# Nucleo.net
KiCad netlist of a schematic drawn in Altium Designer
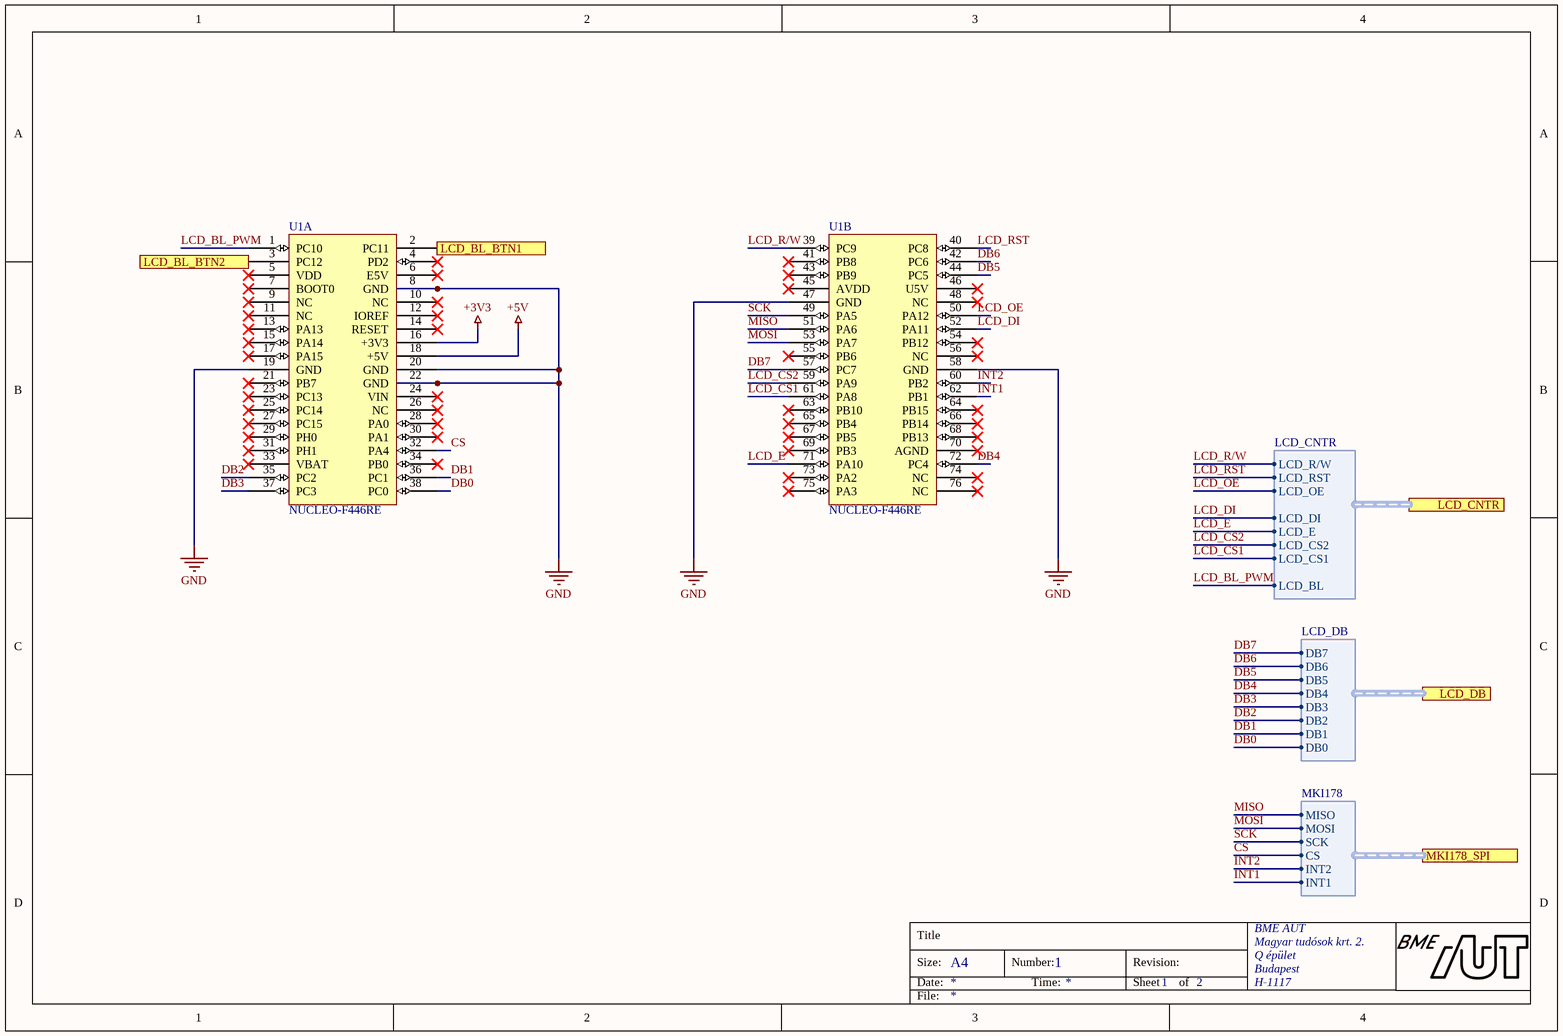
[diagram p0: Nucleo.SchDoc]

(export (version "E")
  (design (tool "Eeschema 10.0.6"))
  (components
    (comp (ref "U1")
      (value "NUCLEO-F446RE")
      (footprint "FP_NUCLEO-64")
      (libsource (lib "hallglib") (part "NUCLEO-F446RE"))
    )
  )
  (nets
    (net (code "4") (name "+3V3") (class "Default")
      (node (ref "U1") (pin "16") (pinfunction "+3V3_16") (pintype "power_in"))
    )
    (net (code "5") (name "+5V") (class "Default")
      (node (ref "U1") (pin "18") (pinfunction "+5V_18") (pintype "power_in"))
    )
    (net (code "6") (name "/CS") (class "Default")
      (node (ref "U1") (pin "32") (pinfunction "PA4_32") (pintype "bidirectional"))
    )
    (net (code "7") (name "/DB0") (class "Default")
      (node (ref "U1") (pin "38") (pinfunction "PC0_38") (pintype "bidirectional"))
    )
    (net (code "8") (name "/DB1") (class "Default")
      (node (ref "U1") (pin "36") (pinfunction "PC1_36") (pintype "bidirectional"))
    )
    (net (code "9") (name "/DB2") (class "Default")
      (node (ref "U1") (pin "35") (pinfunction "PC2_35") (pintype "bidirectional"))
    )
    (net (code "10") (name "/DB3") (class "Default")
      (node (ref "U1") (pin "37") (pinfunction "PC3_37") (pintype "bidirectional"))
    )
    (net (code "11") (name "/DB4") (class "Default")
      (node (ref "U1") (pin "72") (pinfunction "PC4_72") (pintype "bidirectional"))
    )
    (net (code "12") (name "/DB5") (class "Default")
      (node (ref "U1") (pin "44") (pinfunction "PC5_44") (pintype "bidirectional"))
    )
    (net (code "13") (name "/DB6") (class "Default")
      (node (ref "U1") (pin "42") (pinfunction "PC6_42") (pintype "bidirectional"))
    )
    (net (code "14") (name "/DB7") (class "Default")
      (node (ref "U1") (pin "57") (pinfunction "PC7_57") (pintype "bidirectional"))
    )
    (net (code "15") (name "/INT1") (class "Default")
      (node (ref "U1") (pin "62") (pinfunction "PB1_62") (pintype "bidirectional"))
    )
    (net (code "16") (name "/INT2") (class "Default")
      (node (ref "U1") (pin "60") (pinfunction "PB2_60") (pintype "bidirectional"))
    )
    (net (code "17") (name "/LCD_BL_BTN1") (class "Default")
      (node (ref "U1") (pin "2") (pinfunction "PC11_2") (pintype "passive"))
    )
    (net (code "18") (name "/LCD_BL_BTN2") (class "Default")
      (node (ref "U1") (pin "3") (pinfunction "PC12_3") (pintype "passive"))
    )
    (net (code "19") (name "/LCD_BL_PWM") (class "Default")
      (node (ref "U1") (pin "1") (pinfunction "PC10_1") (pintype "bidirectional"))
    )
    (net (code "20") (name "/LCD_CS1") (class "Default")
      (node (ref "U1") (pin "61") (pinfunction "PA8_61") (pintype "bidirectional"))
    )
    (net (code "21") (name "/LCD_CS2") (class "Default")
      (node (ref "U1") (pin "59") (pinfunction "PA9_59") (pintype "bidirectional"))
    )
    (net (code "22") (name "/LCD_DI") (class "Default")
      (node (ref "U1") (pin "52") (pinfunction "PA11_52") (pintype "bidirectional"))
    )
    (net (code "23") (name "/LCD_E") (class "Default")
      (node (ref "U1") (pin "71") (pinfunction "PA10_71") (pintype "bidirectional"))
    )
    (net (code "24") (name "/LCD_OE") (class "Default")
      (node (ref "U1") (pin "50") (pinfunction "PA12_50") (pintype "bidirectional"))
    )
    (net (code "25") (name "/LCD_RST") (class "Default")
      (node (ref "U1") (pin "40") (pinfunction "PC8_40") (pintype "bidirectional"))
    )
    (net (code "26") (name "/LCD_R{slash}W") (class "Default")
      (node (ref "U1") (pin "39") (pinfunction "PC9_39") (pintype "bidirectional"))
    )
    (net (code "27") (name "/MISO") (class "Default")
      (node (ref "U1") (pin "51") (pinfunction "PA6_51") (pintype "bidirectional"))
    )
    (net (code "28") (name "/MOSI") (class "Default")
      (node (ref "U1") (pin "53") (pinfunction "PA7_53") (pintype "bidirectional"))
    )
    (net (code "29") (name "/SCK") (class "Default")
      (node (ref "U1") (pin "49") (pinfunction "PA5_49") (pintype "bidirectional"))
    )
    (net (code "33") (name "GND") (class "Default")
      (node (ref "U1") (pin "19") (pinfunction "GND_19") (pintype "passive"))
      (node (ref "U1") (pin "20") (pinfunction "GND_20") (pintype "passive"))
      (node (ref "U1") (pin "22") (pinfunction "GND_22") (pintype "passive"))
      (node (ref "U1") (pin "47") (pinfunction "GND_47") (pintype "passive"))
      (node (ref "U1") (pin "58") (pinfunction "GND_58") (pintype "passive"))
      (node (ref "U1") (pin "8") (pinfunction "GND_8") (pintype "passive"))
    )
    (net (code "34") (name "unconnected-(U1A-BOOT0-Pad7)") (class "Default")
      (node (ref "U1") (pin "7") (pinfunction "BOOT0_7") (pintype "passive+no_connect"))
    )
    (net (code "35") (name "unconnected-(U1A-E5V-Pad6)") (class "Default")
      (node (ref "U1") (pin "6") (pinfunction "E5V_6") (pintype "power_in+no_connect"))
    )
    (net (code "36") (name "unconnected-(U1A-IOREF-Pad12)") (class "Default")
      (node (ref "U1") (pin "12") (pinfunction "IOREF_12") (pintype "passive+no_connect"))
    )
    (net (code "37") (name "unconnected-(U1A-NC-Pad9)") (class "Default")
      (node (ref "U1") (pin "9") (pinfunction "NC_9") (pintype "passive+no_connect"))
    )
    (net (code "38") (name "unconnected-(U1A-NC-Pad10)") (class "Default")
      (node (ref "U1") (pin "10") (pinfunction "NC_10") (pintype "passive+no_connect"))
    )
    (net (code "39") (name "unconnected-(U1A-NC-Pad11)") (class "Default")
      (node (ref "U1") (pin "11") (pinfunction "NC_11") (pintype "passive+no_connect"))
    )
    (net (code "40") (name "unconnected-(U1A-NC-Pad26)") (class "Default")
      (node (ref "U1") (pin "26") (pinfunction "NC_26") (pintype "passive+no_connect"))
    )
    (net (code "41") (name "unconnected-(U1A-PA0-Pad28)") (class "Default")
      (node (ref "U1") (pin "28") (pinfunction "PA0_28") (pintype "bidirectional+no_connect"))
    )
    (net (code "42") (name "unconnected-(U1A-PA1-Pad30)") (class "Default")
      (node (ref "U1") (pin "30") (pinfunction "PA1_30") (pintype "bidirectional+no_connect"))
    )
    (net (code "43") (name "unconnected-(U1A-PA13-Pad13)") (class "Default")
      (node (ref "U1") (pin "13") (pinfunction "PA13_13") (pintype "bidirectional+no_connect"))
    )
    (net (code "44") (name "unconnected-(U1A-PA14-Pad15)") (class "Default")
      (node (ref "U1") (pin "15") (pinfunction "PA14_15") (pintype "bidirectional+no_connect"))
    )
    (net (code "45") (name "unconnected-(U1A-PA15-Pad17)") (class "Default")
      (node (ref "U1") (pin "17") (pinfunction "PA15_17") (pintype "bidirectional+no_connect"))
    )
    (net (code "46") (name "unconnected-(U1A-PB0-Pad34)") (class "Default")
      (node (ref "U1") (pin "34") (pinfunction "PB0_34") (pintype "bidirectional+no_connect"))
    )
    (net (code "47") (name "unconnected-(U1A-PB7-Pad21)") (class "Default")
      (node (ref "U1") (pin "21") (pinfunction "PB7_21") (pintype "bidirectional+no_connect"))
    )
    (net (code "48") (name "unconnected-(U1A-PC13-Pad23)") (class "Default")
      (node (ref "U1") (pin "23") (pinfunction "PC13_23") (pintype "bidirectional+no_connect"))
    )
    (net (code "49") (name "unconnected-(U1A-PC14-Pad25)") (class "Default")
      (node (ref "U1") (pin "25") (pinfunction "PC14_25") (pintype "bidirectional+no_connect"))
    )
    (net (code "50") (name "unconnected-(U1A-PC15-Pad27)") (class "Default")
      (node (ref "U1") (pin "27") (pinfunction "PC15_27") (pintype "bidirectional+no_connect"))
    )
    (net (code "51") (name "unconnected-(U1A-PD2-Pad4)") (class "Default")
      (node (ref "U1") (pin "4") (pinfunction "PD2_4") (pintype "bidirectional+no_connect"))
    )
    (net (code "52") (name "unconnected-(U1A-PH0-Pad29)") (class "Default")
      (node (ref "U1") (pin "29") (pinfunction "PH0_29") (pintype "bidirectional+no_connect"))
    )
    (net (code "53") (name "unconnected-(U1A-PH1-Pad31)") (class "Default")
      (node (ref "U1") (pin "31") (pinfunction "PH1_31") (pintype "bidirectional+no_connect"))
    )
    (net (code "54") (name "unconnected-(U1A-RESET-Pad14)") (class "Default")
      (node (ref "U1") (pin "14") (pinfunction "RESET_14") (pintype "passive+no_connect"))
    )
    (net (code "55") (name "unconnected-(U1A-VBAT-Pad33)") (class "Default")
      (node (ref "U1") (pin "33") (pinfunction "VBAT_33") (pintype "power_in+no_connect"))
    )
    (net (code "56") (name "unconnected-(U1A-VDD-Pad5)") (class "Default")
      (node (ref "U1") (pin "5") (pinfunction "VDD_5") (pintype "power_in+no_connect"))
    )
    (net (code "57") (name "unconnected-(U1A-VIN-Pad24)") (class "Default")
      (node (ref "U1") (pin "24") (pinfunction "VIN_24") (pintype "power_in+no_connect"))
    )
    (net (code "58") (name "unconnected-(U1B-AGND-Pad70)") (class "Default")
      (node (ref "U1") (pin "70") (pinfunction "AGND_70") (pintype "passive+no_connect"))
    )
    (net (code "59") (name "unconnected-(U1B-AVDD-Pad45)") (class "Default")
      (node (ref "U1") (pin "45") (pinfunction "AVDD_45") (pintype "power_in+no_connect"))
    )
    (net (code "60") (name "unconnected-(U1B-NC-Pad48)") (class "Default")
      (node (ref "U1") (pin "48") (pinfunction "NC_48") (pintype "passive+no_connect"))
    )
    (net (code "61") (name "unconnected-(U1B-NC-Pad56)") (class "Default")
      (node (ref "U1") (pin "56") (pinfunction "NC_56") (pintype "passive+no_connect"))
    )
    (net (code "62") (name "unconnected-(U1B-NC-Pad74)") (class "Default")
      (node (ref "U1") (pin "74") (pinfunction "NC_74") (pintype "passive+no_connect"))
    )
    (net (code "63") (name "unconnected-(U1B-NC-Pad76)") (class "Default")
      (node (ref "U1") (pin "76") (pinfunction "NC_76") (pintype "passive+no_connect"))
    )
    (net (code "64") (name "unconnected-(U1B-PA2-Pad73)") (class "Default")
      (node (ref "U1") (pin "73") (pinfunction "PA2_73") (pintype "bidirectional+no_connect"))
    )
    (net (code "65") (name "unconnected-(U1B-PA3-Pad75)") (class "Default")
      (node (ref "U1") (pin "75") (pinfunction "PA3_75") (pintype "bidirectional+no_connect"))
    )
    (net (code "66") (name "unconnected-(U1B-PB3-Pad69)") (class "Default")
      (node (ref "U1") (pin "69") (pinfunction "PB3_69") (pintype "bidirectional+no_connect"))
    )
    (net (code "67") (name "unconnected-(U1B-PB4-Pad65)") (class "Default")
      (node (ref "U1") (pin "65") (pinfunction "PB4_65") (pintype "bidirectional+no_connect"))
    )
    (net (code "68") (name "unconnected-(U1B-PB5-Pad67)") (class "Default")
      (node (ref "U1") (pin "67") (pinfunction "PB5_67") (pintype "bidirectional+no_connect"))
    )
    (net (code "69") (name "unconnected-(U1B-PB6-Pad55)") (class "Default")
      (node (ref "U1") (pin "55") (pinfunction "PB6_55") (pintype "bidirectional+no_connect"))
    )
    (net (code "70") (name "unconnected-(U1B-PB8-Pad41)") (class "Default")
      (node (ref "U1") (pin "41") (pinfunction "PB8_41") (pintype "bidirectional+no_connect"))
    )
    (net (code "71") (name "unconnected-(U1B-PB9-Pad43)") (class "Default")
      (node (ref "U1") (pin "43") (pinfunction "PB9_43") (pintype "bidirectional+no_connect"))
    )
    (net (code "72") (name "unconnected-(U1B-PB10-Pad63)") (class "Default")
      (node (ref "U1") (pin "63") (pinfunction "PB10_63") (pintype "bidirectional+no_connect"))
    )
    (net (code "73") (name "unconnected-(U1B-PB12-Pad54)") (class "Default")
      (node (ref "U1") (pin "54") (pinfunction "PB12_54") (pintype "bidirectional+no_connect"))
    )
    (net (code "74") (name "unconnected-(U1B-PB13-Pad68)") (class "Default")
      (node (ref "U1") (pin "68") (pinfunction "PB13_68") (pintype "bidirectional+no_connect"))
    )
    (net (code "75") (name "unconnected-(U1B-PB14-Pad66)") (class "Default")
      (node (ref "U1") (pin "66") (pinfunction "PB14_66") (pintype "bidirectional+no_connect"))
    )
    (net (code "76") (name "unconnected-(U1B-PB15-Pad64)") (class "Default")
      (node (ref "U1") (pin "64") (pinfunction "PB15_64") (pintype "bidirectional+no_connect"))
    )
    (net (code "77") (name "unconnected-(U1B-U5V-Pad46)") (class "Default")
      (node (ref "U1") (pin "46") (pinfunction "U5V_46") (pintype "power_in+no_connect"))
    )
  )
)
